# double.net
KiCad netlist of a schematic drawn in EAGLE
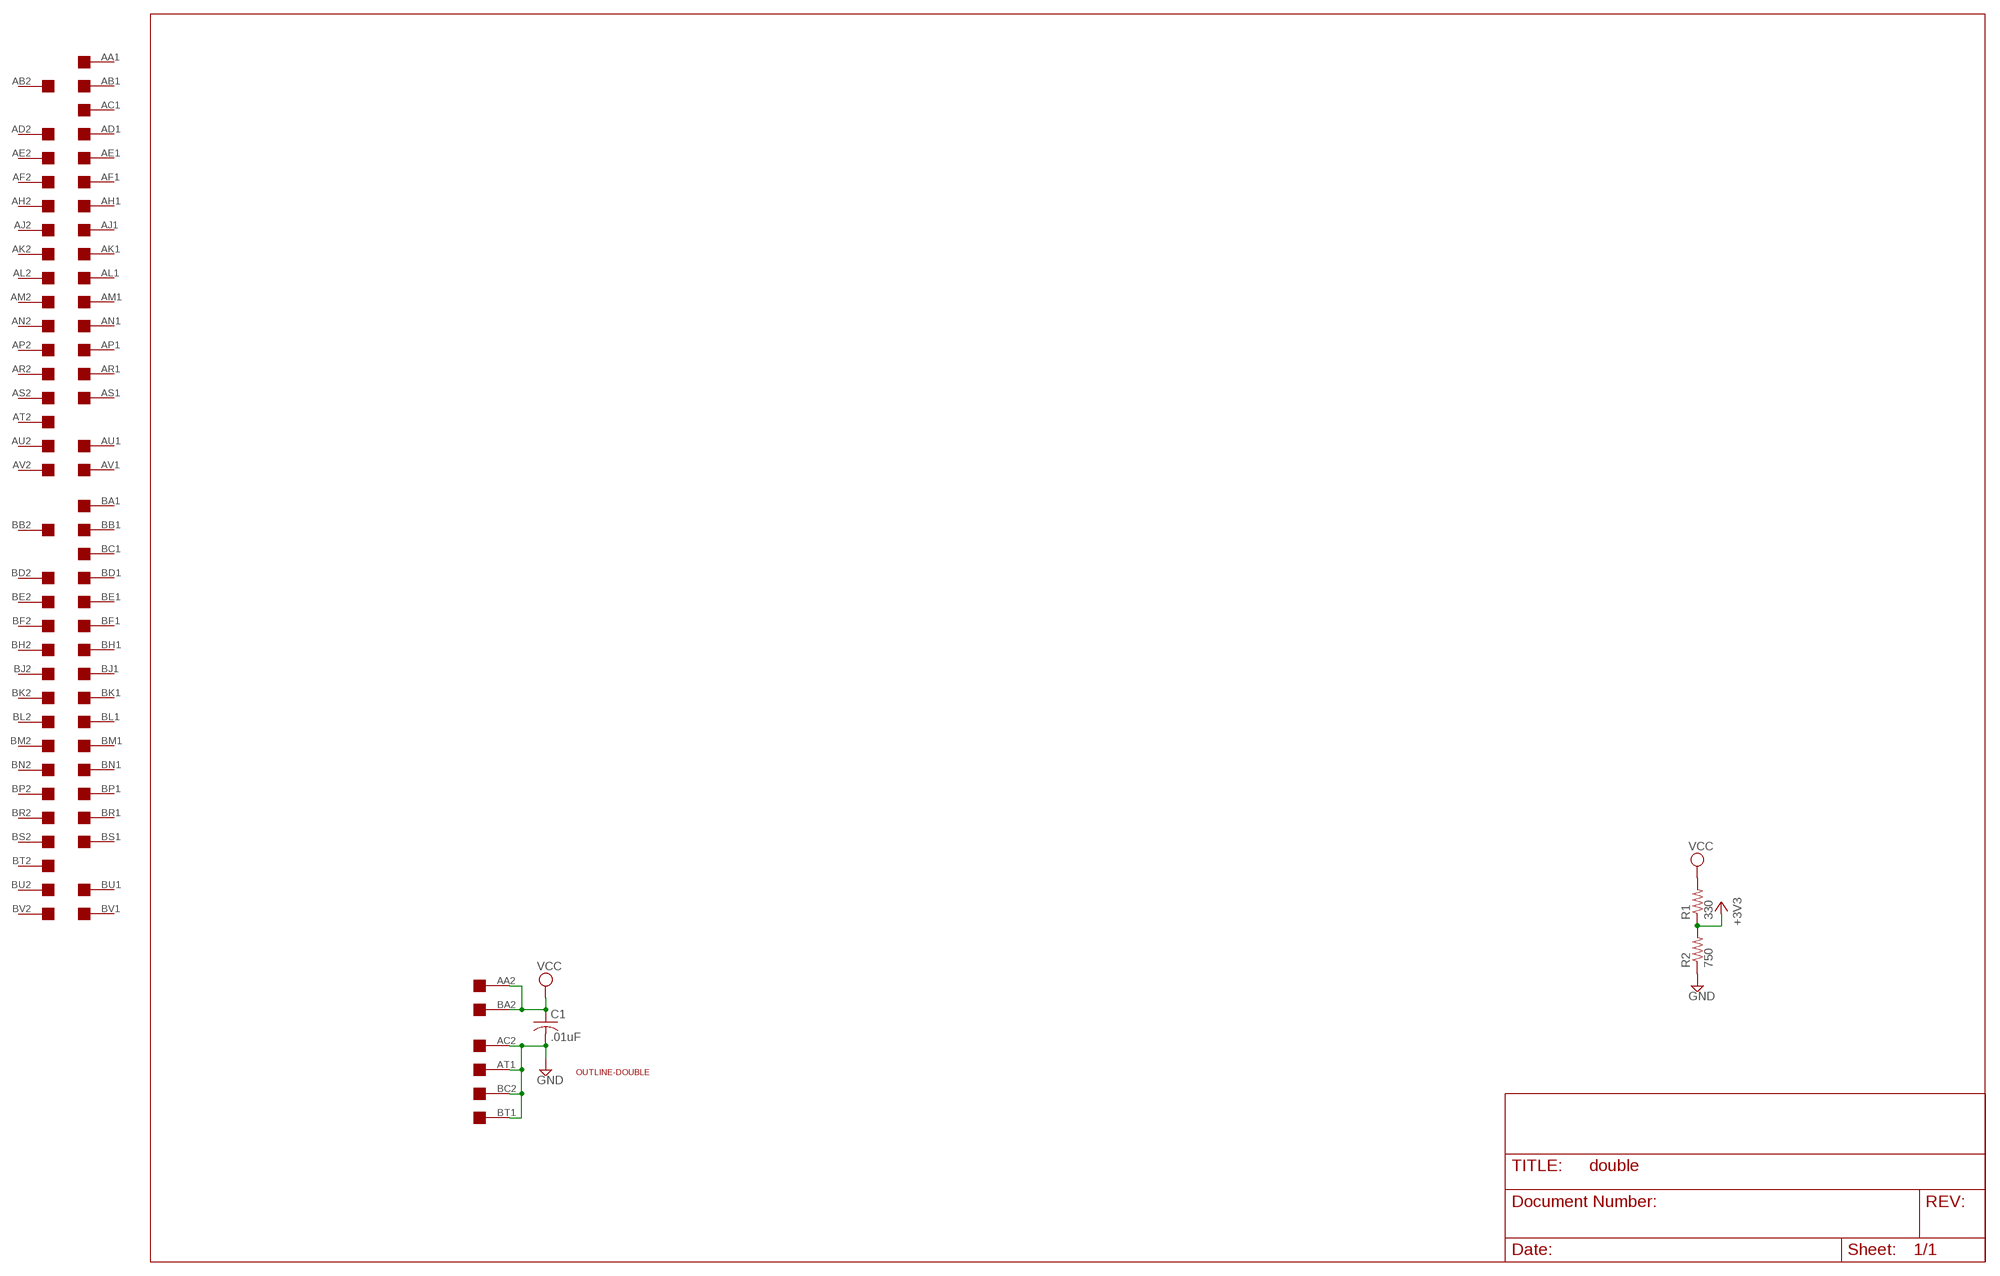
[diagram p0: schematic, sheet 1]

(export (version "E")
  (design (tool "Eeschema 10.0.6"))
  (components
    (comp (ref "C1")
      (value ".01uF")
      (footprint "eagle-import:C050-025X075")
      (libsource (lib "eagle-import") (part "C-US050-025X075"))
    )
    (comp (ref "R1")
      (value "330")
      (footprint "eagle-import:0207_10")
      (libsource (lib "eagle-import") (part "R-US_0207/10"))
    )
    (comp (ref "R2")
      (value "750")
      (footprint "eagle-import:0207_10")
      (libsource (lib "eagle-import") (part "R-US_0207/10"))
    )
    (comp (ref "U$1")
      (value "OUTLINE-DOUBLE")
      (footprint "eagle-import:DOUBLE")
      (libsource (lib "eagle-import") (part "OUTLINE-DOUBLE"))
    )
    (comp (ref "U$3")
      (value "DOUBLE")
      (footprint "eagle-import:EDGE-CON4")
      (libsource (lib "eagle-import") (part "DOUBLE"))
    )
  )
  (nets
    (net (code "1") (name "+3V3") (class "Default")
      (node (ref "R1") (pin "1") (pinfunction "1_1") (pintype "passive"))
      (node (ref "R2") (pin "2") (pinfunction "2_2") (pintype "passive"))
    )
    (net (code "2") (name "GND") (class "Default")
      (node (ref "C1") (pin "2") (pinfunction "2_2") (pintype "passive"))
      (node (ref "R2") (pin "1") (pinfunction "1_1") (pintype "passive"))
      (node (ref "U$3") (pin "AC2") (pinfunction "1_AC2") (pintype "bidirectional"))
      (node (ref "U$3") (pin "AT1") (pinfunction "1_AT1") (pintype "bidirectional"))
      (node (ref "U$3") (pin "BC2") (pinfunction "1_BC2") (pintype "bidirectional"))
      (node (ref "U$3") (pin "BT1") (pinfunction "1_BT1") (pintype "bidirectional"))
    )
    (net (code "3") (name "VCC") (class "Default")
      (node (ref "C1") (pin "1") (pinfunction "1_1") (pintype "passive"))
      (node (ref "R1") (pin "2") (pinfunction "2_2") (pintype "passive"))
      (node (ref "U$3") (pin "AA2") (pinfunction "1_AA2") (pintype "bidirectional"))
      (node (ref "U$3") (pin "BA2") (pinfunction "1_BA2") (pintype "bidirectional"))
    )
    (net (code "4") (name "unconnected-(U$3A-1-PadAA1)") (class "Default")
      (node (ref "U$3") (pin "AA1") (pinfunction "1_AA1") (pintype "bidirectional"))
    )
    (net (code "5") (name "unconnected-(U$3AA-1-PadAR1)") (class "Default")
      (node (ref "U$3") (pin "AR1") (pinfunction "1_AR1") (pintype "bidirectional"))
    )
    (net (code "6") (name "unconnected-(U$3AB-1-PadAR2)") (class "Default")
      (node (ref "U$3") (pin "AR2") (pinfunction "1_AR2") (pintype "bidirectional"))
    )
    (net (code "7") (name "unconnected-(U$3AC-1-PadAS1)") (class "Default")
      (node (ref "U$3") (pin "AS1") (pinfunction "1_AS1") (pintype "bidirectional"))
    )
    (net (code "8") (name "unconnected-(U$3AD-1-PadAS2)") (class "Default")
      (node (ref "U$3") (pin "AS2") (pinfunction "1_AS2") (pintype "bidirectional"))
    )
    (net (code "9") (name "unconnected-(U$3AF-1-PadAT2)") (class "Default")
      (node (ref "U$3") (pin "AT2") (pinfunction "1_AT2") (pintype "bidirectional"))
    )
    (net (code "10") (name "unconnected-(U$3AG-1-PadAU1)") (class "Default")
      (node (ref "U$3") (pin "AU1") (pinfunction "1_AU1") (pintype "bidirectional"))
    )
    (net (code "11") (name "unconnected-(U$3AH-1-PadAU2)") (class "Default")
      (node (ref "U$3") (pin "AU2") (pinfunction "1_AU2") (pintype "bidirectional"))
    )
    (net (code "12") (name "unconnected-(U$3AI-1-PadAV1)") (class "Default")
      (node (ref "U$3") (pin "AV1") (pinfunction "1_AV1") (pintype "bidirectional"))
    )
    (net (code "13") (name "unconnected-(U$3AJ-1-PadAV2)") (class "Default")
      (node (ref "U$3") (pin "AV2") (pinfunction "1_AV2") (pintype "bidirectional"))
    )
    (net (code "14") (name "unconnected-(U$3AK-1-PadBA1)") (class "Default")
      (node (ref "U$3") (pin "BA1") (pinfunction "1_BA1") (pintype "bidirectional"))
    )
    (net (code "15") (name "unconnected-(U$3AM-1-PadBB1)") (class "Default")
      (node (ref "U$3") (pin "BB1") (pinfunction "1_BB1") (pintype "bidirectional"))
    )
    (net (code "16") (name "unconnected-(U$3AN-1-PadBB2)") (class "Default")
      (node (ref "U$3") (pin "BB2") (pinfunction "1_BB2") (pintype "bidirectional"))
    )
    (net (code "17") (name "unconnected-(U$3AO-1-PadBC1)") (class "Default")
      (node (ref "U$3") (pin "BC1") (pinfunction "1_BC1") (pintype "bidirectional"))
    )
    (net (code "18") (name "unconnected-(U$3AQ-1-PadBD1)") (class "Default")
      (node (ref "U$3") (pin "BD1") (pinfunction "1_BD1") (pintype "bidirectional"))
    )
    (net (code "19") (name "unconnected-(U$3AR-1-PadBD2)") (class "Default")
      (node (ref "U$3") (pin "BD2") (pinfunction "1_BD2") (pintype "bidirectional"))
    )
    (net (code "20") (name "unconnected-(U$3AS-1-PadBE1)") (class "Default")
      (node (ref "U$3") (pin "BE1") (pinfunction "1_BE1") (pintype "bidirectional"))
    )
    (net (code "21") (name "unconnected-(U$3AT-1-PadBE2)") (class "Default")
      (node (ref "U$3") (pin "BE2") (pinfunction "1_BE2") (pintype "bidirectional"))
    )
    (net (code "22") (name "unconnected-(U$3AU-1-PadBF1)") (class "Default")
      (node (ref "U$3") (pin "BF1") (pinfunction "1_BF1") (pintype "bidirectional"))
    )
    (net (code "23") (name "unconnected-(U$3AV-1-PadBF2)") (class "Default")
      (node (ref "U$3") (pin "BF2") (pinfunction "1_BF2") (pintype "bidirectional"))
    )
    (net (code "24") (name "unconnected-(U$3AW-1-PadBH1)") (class "Default")
      (node (ref "U$3") (pin "BH1") (pinfunction "1_BH1") (pintype "bidirectional"))
    )
    (net (code "25") (name "unconnected-(U$3AX-1-PadBH2)") (class "Default")
      (node (ref "U$3") (pin "BH2") (pinfunction "1_BH2") (pintype "bidirectional"))
    )
    (net (code "26") (name "unconnected-(U$3AY-1-PadBJ1)") (class "Default")
      (node (ref "U$3") (pin "BJ1") (pinfunction "1_BJ1") (pintype "bidirectional"))
    )
    (net (code "27") (name "unconnected-(U$3AZ-1-PadBJ2)") (class "Default")
      (node (ref "U$3") (pin "BJ2") (pinfunction "1_BJ2") (pintype "bidirectional"))
    )
    (net (code "28") (name "unconnected-(U$3BA-1-PadBK1)") (class "Default")
      (node (ref "U$3") (pin "BK1") (pinfunction "1_BK1") (pintype "bidirectional"))
    )
    (net (code "29") (name "unconnected-(U$3BB-1-PadBK2)") (class "Default")
      (node (ref "U$3") (pin "BK2") (pinfunction "1_BK2") (pintype "bidirectional"))
    )
    (net (code "30") (name "unconnected-(U$3BC-1-PadBL1)") (class "Default")
      (node (ref "U$3") (pin "BL1") (pinfunction "1_BL1") (pintype "bidirectional"))
    )
    (net (code "31") (name "unconnected-(U$3BD-1-PadBL2)") (class "Default")
      (node (ref "U$3") (pin "BL2") (pinfunction "1_BL2") (pintype "bidirectional"))
    )
    (net (code "32") (name "unconnected-(U$3BE-1-PadBM1)") (class "Default")
      (node (ref "U$3") (pin "BM1") (pinfunction "1_BM1") (pintype "bidirectional"))
    )
    (net (code "33") (name "unconnected-(U$3BF-1-PadBM2)") (class "Default")
      (node (ref "U$3") (pin "BM2") (pinfunction "1_BM2") (pintype "bidirectional"))
    )
    (net (code "34") (name "unconnected-(U$3BG-1-PadBN1)") (class "Default")
      (node (ref "U$3") (pin "BN1") (pinfunction "1_BN1") (pintype "bidirectional"))
    )
    (net (code "35") (name "unconnected-(U$3BH-1-PadBN2)") (class "Default")
      (node (ref "U$3") (pin "BN2") (pinfunction "1_BN2") (pintype "bidirectional"))
    )
    (net (code "36") (name "unconnected-(U$3BI-1-PadBP1)") (class "Default")
      (node (ref "U$3") (pin "BP1") (pinfunction "1_BP1") (pintype "bidirectional"))
    )
    (net (code "37") (name "unconnected-(U$3BJ-1-PadBP2)") (class "Default")
      (node (ref "U$3") (pin "BP2") (pinfunction "1_BP2") (pintype "bidirectional"))
    )
    (net (code "38") (name "unconnected-(U$3BK-1-PadBR1)") (class "Default")
      (node (ref "U$3") (pin "BR1") (pinfunction "1_BR1") (pintype "bidirectional"))
    )
    (net (code "39") (name "unconnected-(U$3BL-1-PadBR2)") (class "Default")
      (node (ref "U$3") (pin "BR2") (pinfunction "1_BR2") (pintype "bidirectional"))
    )
    (net (code "40") (name "unconnected-(U$3BM-1-PadBS1)") (class "Default")
      (node (ref "U$3") (pin "BS1") (pinfunction "1_BS1") (pintype "bidirectional"))
    )
    (net (code "41") (name "unconnected-(U$3BN-1-PadBS2)") (class "Default")
      (node (ref "U$3") (pin "BS2") (pinfunction "1_BS2") (pintype "bidirectional"))
    )
    (net (code "42") (name "unconnected-(U$3BP-1-PadBT2)") (class "Default")
      (node (ref "U$3") (pin "BT2") (pinfunction "1_BT2") (pintype "bidirectional"))
    )
    (net (code "43") (name "unconnected-(U$3BQ-1-PadBU1)") (class "Default")
      (node (ref "U$3") (pin "BU1") (pinfunction "1_BU1") (pintype "bidirectional"))
    )
    (net (code "44") (name "unconnected-(U$3BR-1-PadBU2)") (class "Default")
      (node (ref "U$3") (pin "BU2") (pinfunction "1_BU2") (pintype "bidirectional"))
    )
    (net (code "45") (name "unconnected-(U$3BS-1-PadBV1)") (class "Default")
      (node (ref "U$3") (pin "BV1") (pinfunction "1_BV1") (pintype "bidirectional"))
    )
    (net (code "46") (name "unconnected-(U$3BT-1-PadBV2)") (class "Default")
      (node (ref "U$3") (pin "BV2") (pinfunction "1_BV2") (pintype "bidirectional"))
    )
    (net (code "47") (name "unconnected-(U$3C-1-PadAB1)") (class "Default")
      (node (ref "U$3") (pin "AB1") (pinfunction "1_AB1") (pintype "bidirectional"))
    )
    (net (code "48") (name "unconnected-(U$3D-1-PadAB2)") (class "Default")
      (node (ref "U$3") (pin "AB2") (pinfunction "1_AB2") (pintype "bidirectional"))
    )
    (net (code "49") (name "unconnected-(U$3E-1-PadAC1)") (class "Default")
      (node (ref "U$3") (pin "AC1") (pinfunction "1_AC1") (pintype "bidirectional"))
    )
    (net (code "50") (name "unconnected-(U$3G-1-PadAD1)") (class "Default")
      (node (ref "U$3") (pin "AD1") (pinfunction "1_AD1") (pintype "bidirectional"))
    )
    (net (code "51") (name "unconnected-(U$3H-1-PadAD2)") (class "Default")
      (node (ref "U$3") (pin "AD2") (pinfunction "1_AD2") (pintype "bidirectional"))
    )
    (net (code "52") (name "unconnected-(U$3I-1-PadAE1)") (class "Default")
      (node (ref "U$3") (pin "AE1") (pinfunction "1_AE1") (pintype "bidirectional"))
    )
    (net (code "53") (name "unconnected-(U$3J-1-PadAE2)") (class "Default")
      (node (ref "U$3") (pin "AE2") (pinfunction "1_AE2") (pintype "bidirectional"))
    )
    (net (code "54") (name "unconnected-(U$3K-1-PadAF1)") (class "Default")
      (node (ref "U$3") (pin "AF1") (pinfunction "1_AF1") (pintype "bidirectional"))
    )
    (net (code "55") (name "unconnected-(U$3L-1-PadAF2)") (class "Default")
      (node (ref "U$3") (pin "AF2") (pinfunction "1_AF2") (pintype "bidirectional"))
    )
    (net (code "56") (name "unconnected-(U$3M-1-PadAH1)") (class "Default")
      (node (ref "U$3") (pin "AH1") (pinfunction "1_AH1") (pintype "bidirectional"))
    )
    (net (code "57") (name "unconnected-(U$3N-1-PadAH2)") (class "Default")
      (node (ref "U$3") (pin "AH2") (pinfunction "1_AH2") (pintype "bidirectional"))
    )
    (net (code "58") (name "unconnected-(U$3O-1-PadAJ1)") (class "Default")
      (node (ref "U$3") (pin "AJ1") (pinfunction "1_AJ1") (pintype "bidirectional"))
    )
    (net (code "59") (name "unconnected-(U$3P-1-PadAJ2)") (class "Default")
      (node (ref "U$3") (pin "AJ2") (pinfunction "1_AJ2") (pintype "bidirectional"))
    )
    (net (code "60") (name "unconnected-(U$3Q-1-PadAK1)") (class "Default")
      (node (ref "U$3") (pin "AK1") (pinfunction "1_AK1") (pintype "bidirectional"))
    )
    (net (code "61") (name "unconnected-(U$3R-1-PadAK2)") (class "Default")
      (node (ref "U$3") (pin "AK2") (pinfunction "1_AK2") (pintype "bidirectional"))
    )
    (net (code "62") (name "unconnected-(U$3S-1-PadAL1)") (class "Default")
      (node (ref "U$3") (pin "AL1") (pinfunction "1_AL1") (pintype "bidirectional"))
    )
    (net (code "63") (name "unconnected-(U$3T-1-PadAL2)") (class "Default")
      (node (ref "U$3") (pin "AL2") (pinfunction "1_AL2") (pintype "bidirectional"))
    )
    (net (code "64") (name "unconnected-(U$3U-1-PadAM1)") (class "Default")
      (node (ref "U$3") (pin "AM1") (pinfunction "1_AM1") (pintype "bidirectional"))
    )
    (net (code "65") (name "unconnected-(U$3V-1-PadAM2)") (class "Default")
      (node (ref "U$3") (pin "AM2") (pinfunction "1_AM2") (pintype "bidirectional"))
    )
    (net (code "66") (name "unconnected-(U$3W-1-PadAN1)") (class "Default")
      (node (ref "U$3") (pin "AN1") (pinfunction "1_AN1") (pintype "bidirectional"))
    )
    (net (code "67") (name "unconnected-(U$3X-1-PadAN2)") (class "Default")
      (node (ref "U$3") (pin "AN2") (pinfunction "1_AN2") (pintype "bidirectional"))
    )
    (net (code "68") (name "unconnected-(U$3Y-1-PadAP1)") (class "Default")
      (node (ref "U$3") (pin "AP1") (pinfunction "1_AP1") (pintype "bidirectional"))
    )
    (net (code "69") (name "unconnected-(U$3Z-1-PadAP2)") (class "Default")
      (node (ref "U$3") (pin "AP2") (pinfunction "1_AP2") (pintype "bidirectional"))
    )
  )
)
